# BatteryMonitor.net
KiCad netlist of a schematic drawn in Altium Designer
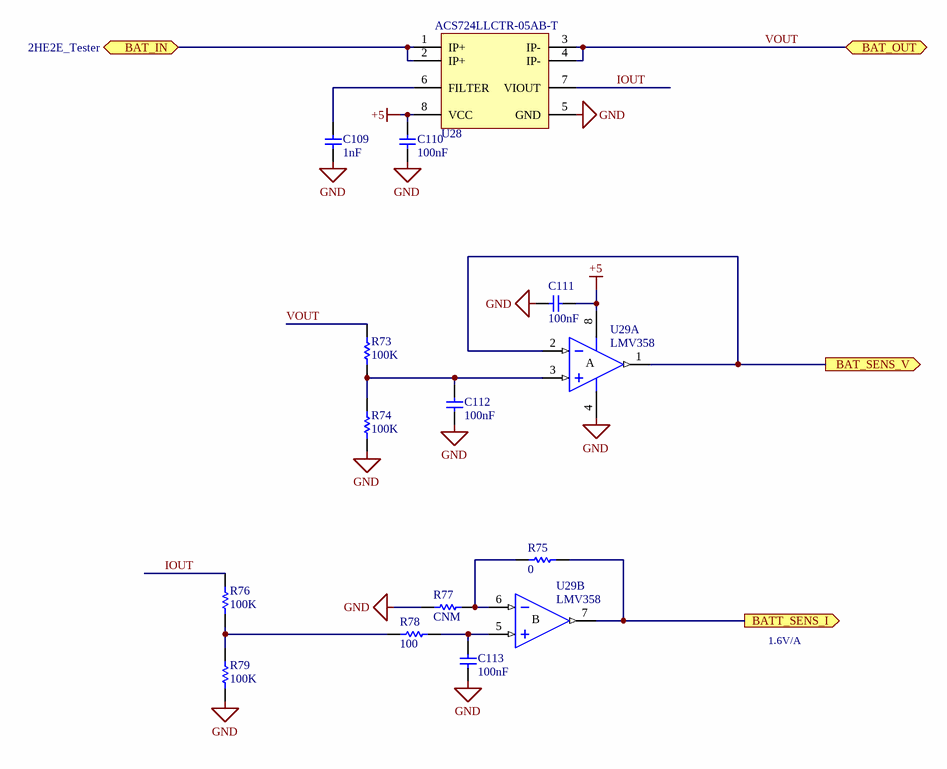
[diagram p0: BatteryMonitor.SchDoc]

(export (version "E")
  (design (tool "Eeschema 10.0.6"))
  (components
    (comp (ref "C109")
      (value "1nF")
      (footprint "0603M")
      (description "Ceramic Capacitor 25V")
      (fields (field (name "Comment") "Cap Ceramic"))
      (libsource (lib "Plume") (part "Cap Ceramic"))
    )
    (comp (ref "C110")
      (value "100nF")
      (footprint "0603M")
      (description "Ceramic Capacitor 25V")
      (fields (field (name "Comment") "Cap Ceramic"))
      (libsource (lib "Plume") (part "Cap Ceramic"))
    )
    (comp (ref "C111")
      (value "100nF")
      (footprint "0603M")
      (description "Ceramic Capacitor 25V")
      (fields (field (name "Comment") "Cap Ceramic"))
      (libsource (lib "Plume") (part "Cap Ceramic"))
    )
    (comp (ref "C112")
      (value "100nF")
      (footprint "0603M")
      (description "Ceramic Capacitor 25V")
      (fields (field (name "Comment") "Cap Ceramic"))
      (libsource (lib "Plume") (part "Cap Ceramic"))
    )
    (comp (ref "C113")
      (value "100nF")
      (footprint "0603M")
      (description "Ceramic Capacitor 25V")
      (fields (field (name "Comment") "Cap Ceramic"))
      (libsource (lib "Plume") (part "Cap Ceramic"))
    )
    (comp (ref "R73")
      (value "100K")
      (footprint "0603M")
      (description "Resistor")
      (libsource (lib "Plume") (part "Resistor"))
    )
    (comp (ref "R74")
      (value "100K")
      (footprint "0603M")
      (description "Resistor")
      (libsource (lib "Plume") (part "Resistor"))
    )
    (comp (ref "R75")
      (value "0")
      (footprint "0603M")
      (description "Resistor")
      (libsource (lib "Plume") (part "Resistor"))
    )
    (comp (ref "R76")
      (value "100K")
      (footprint "0603M")
      (description "Resistor")
      (libsource (lib "Plume") (part "Resistor"))
    )
    (comp (ref "R77")
      (value "CNM")
      (footprint "0603M")
      (description "Resistor")
      (libsource (lib "Plume") (part "Resistor"))
    )
    (comp (ref "R78")
      (value "100")
      (footprint "0603M")
      (description "Resistor")
      (libsource (lib "Plume") (part "Resistor"))
    )
    (comp (ref "R79")
      (value "100K")
      (footprint "0603M")
      (description "Resistor")
      (libsource (lib "Plume") (part "Resistor"))
    )
    (comp (ref "U28")
      (value "ACS724LLCTR-05AB-T")
      (footprint "SOIC127P600-8N")
      (description "Automotive-Grade, Galvanically Isolated Current Sensor IC with Common-Mode Field Rejection")
      (libsource (lib "Plume") (part "ACS724LLCTR-xxxx"))
    )
    (comp (ref "U29")
      (value "LMV358")
      (footprint "SOIC127P600-8N")
      (description "Dual Operational Amplifier Single Supply Rail to Rail")
      (fields (field (name "PUBLISHER") "Altium Limited"))
      (libsource (lib "Plume") (part "LMV358"))
    )
  )
  (nets
    (net (code "1") (name "+5") (class "Default")
      (node (ref "C110") (pin "2") (pinfunction "2_2") (pintype "passive"))
      (node (ref "C111") (pin "2") (pinfunction "2_2") (pintype "passive"))
      (node (ref "U28") (pin "8") (pinfunction "VCC_8") (pintype "passive"))
      (node (ref "U29") (pin "8") (pinfunction "V+_8") (pintype "power_in"))
    )
    (net (code "2") (name "/BATT_SENS_I") (class "Default")
      (node (ref "R75") (pin "1") (pinfunction "1_1") (pintype "passive"))
      (node (ref "U29") (pin "7") (pinfunction "OUT_7") (pintype "output"))
    )
    (net (code "3") (name "/BAT_IN") (class "Default")
      (node (ref "U28") (pin "1") (pinfunction "IP+_1") (pintype "passive"))
      (node (ref "U28") (pin "2") (pinfunction "IP+_2") (pintype "passive"))
    )
    (net (code "4") (name "/BAT_SENS_V") (class "Default")
      (node (ref "U29") (pin "1") (pinfunction "OUT_1") (pintype "output"))
      (node (ref "U29") (pin "2") (pinfunction "IN-_2") (pintype "input"))
    )
    (net (code "5") (name "/IOUT") (class "Default")
      (node (ref "R76") (pin "1") (pinfunction "1_1") (pintype "passive"))
      (node (ref "U28") (pin "7") (pinfunction "VIOUT_7") (pintype "passive"))
    )
    (net (code "6") (name "/VOUT") (class "Default")
      (node (ref "R73") (pin "2") (pinfunction "2_2") (pintype "passive"))
      (node (ref "U28") (pin "3") (pinfunction "IP-_3") (pintype "passive"))
      (node (ref "U28") (pin "4") (pinfunction "IP-_4") (pintype "passive"))
    )
    (net (code "7") (name "GND") (class "Default")
      (node (ref "C109") (pin "1") (pinfunction "1_1") (pintype "passive"))
      (node (ref "C110") (pin "1") (pinfunction "1_1") (pintype "passive"))
      (node (ref "C111") (pin "1") (pinfunction "1_1") (pintype "passive"))
      (node (ref "C112") (pin "1") (pinfunction "1_1") (pintype "passive"))
      (node (ref "C113") (pin "1") (pinfunction "1_1") (pintype "passive"))
      (node (ref "R74") (pin "1") (pinfunction "1_1") (pintype "passive"))
      (node (ref "R77") (pin "2") (pinfunction "2_2") (pintype "passive"))
      (node (ref "R79") (pin "2") (pinfunction "2_2") (pintype "passive"))
      (node (ref "U28") (pin "5") (pinfunction "GND_5") (pintype "passive"))
      (node (ref "U29") (pin "4") (pinfunction "GND_4") (pintype "passive"))
    )
    (net (code "8") (name "Net-(R76-Pad2)") (class "Default")
      (node (ref "R76") (pin "2") (pinfunction "2_2") (pintype "passive"))
      (node (ref "R78") (pin "2") (pinfunction "2_2") (pintype "passive"))
      (node (ref "R79") (pin "1") (pinfunction "1_1") (pintype "passive"))
    )
    (net (code "9") (name "Net-(U28-FILTER)") (class "Default")
      (node (ref "C109") (pin "2") (pinfunction "2_2") (pintype "passive"))
      (node (ref "U28") (pin "6") (pinfunction "FILTER_6") (pintype "passive"))
    )
    (net (code "10") (name "Net-(U29A-IN+)") (class "Default")
      (node (ref "C112") (pin "2") (pinfunction "2_2") (pintype "passive"))
      (node (ref "R73") (pin "1") (pinfunction "1_1") (pintype "passive"))
      (node (ref "R74") (pin "2") (pinfunction "2_2") (pintype "passive"))
      (node (ref "U29") (pin "3") (pinfunction "IN+_3") (pintype "input"))
    )
    (net (code "11") (name "Net-(U29B-IN+)") (class "Default")
      (node (ref "C113") (pin "2") (pinfunction "2_2") (pintype "passive"))
      (node (ref "R78") (pin "1") (pinfunction "1_1") (pintype "passive"))
      (node (ref "U29") (pin "5") (pinfunction "IN+_5") (pintype "input"))
    )
    (net (code "12") (name "Net-(U29B-IN-)") (class "Default")
      (node (ref "R75") (pin "2") (pinfunction "2_2") (pintype "passive"))
      (node (ref "R77") (pin "1") (pinfunction "1_1") (pintype "passive"))
      (node (ref "U29") (pin "6") (pinfunction "IN-_6") (pintype "input"))
    )
  )
)
